# NeatoLDS_Breakout_Board_v0_1.net
KiCad netlist of a schematic drawn in EAGLE
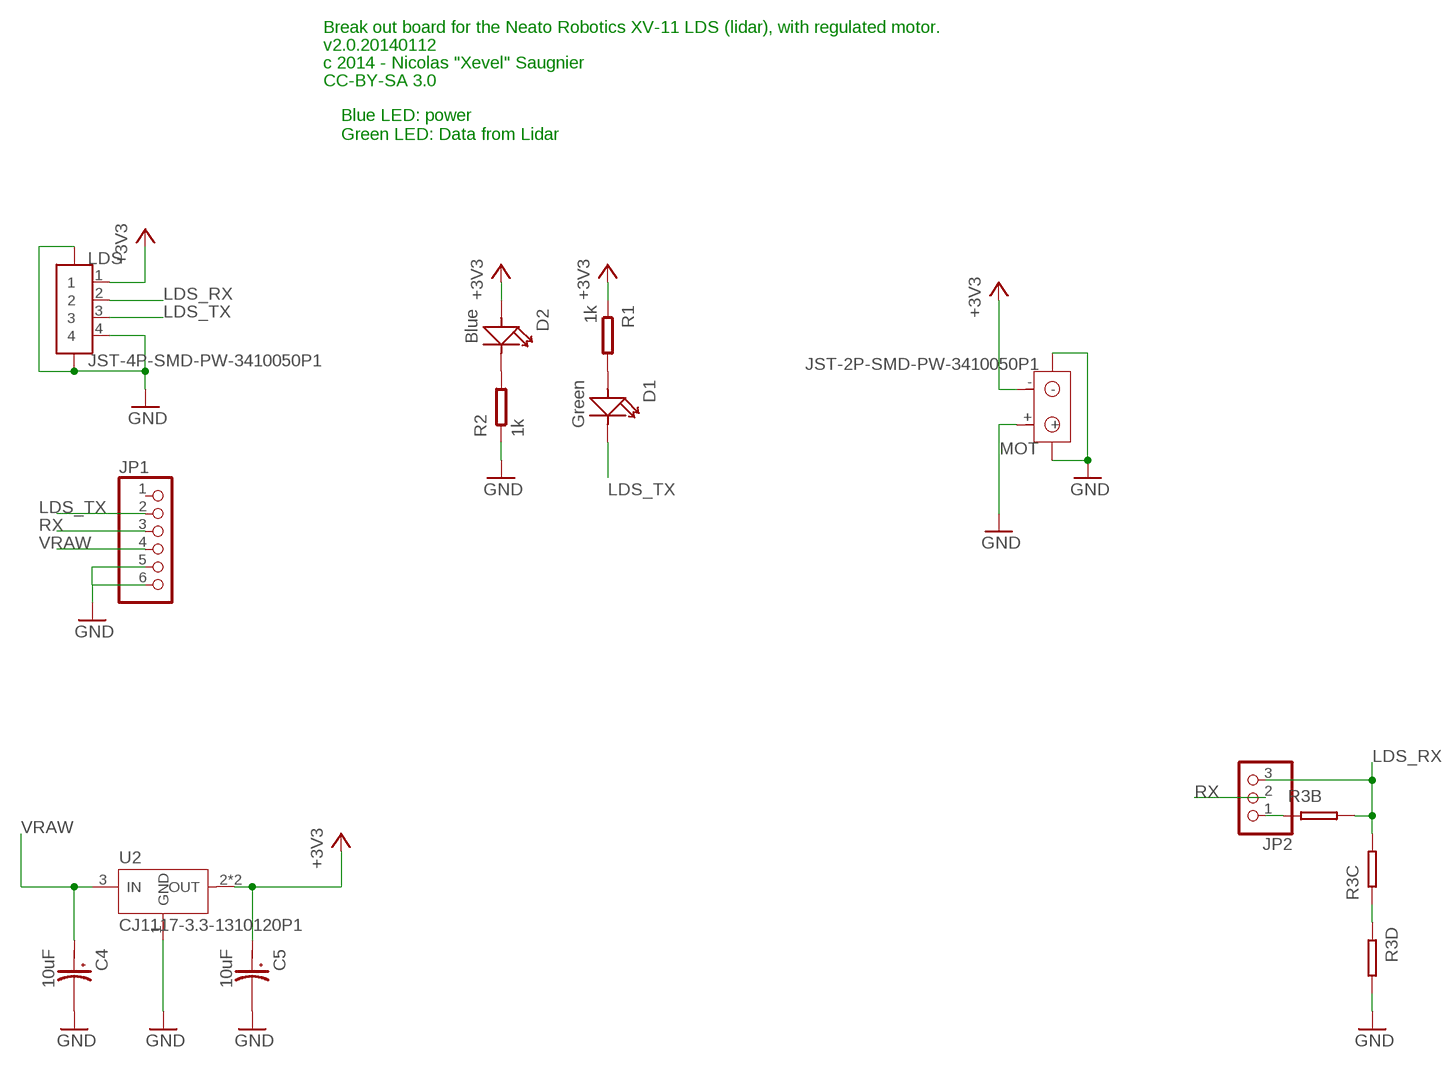
[diagram p0: schematic, sheet 1]

(export (version "E")
  (design (tool "Eeschema 10.0.6"))
  (components
    (comp (ref "C4")
      (value "10uF")
      (footprint "eagle-import:AVX-A")
      (libsource (lib "eagle-import") (part "C-POLAR-A"))
    )
    (comp (ref "C5")
      (value "10uF")
      (footprint "eagle-import:AVX-A")
      (libsource (lib "eagle-import") (part "C-POLAR-A"))
    )
    (comp (ref "D1")
      (value "Green")
      (footprint "eagle-import:LED0603")
      (libsource (lib "eagle-import") (part "LED"))
    )
    (comp (ref "D2")
      (value "Blue")
      (footprint "eagle-import:LED0603")
      (libsource (lib "eagle-import") (part "LED"))
    )
    (comp (ref "JP1")
      (value "PINHD-1X6")
      (footprint "eagle-import:1X06")
      (libsource (lib "eagle-import") (part "PINHD-1X6"))
    )
    (comp (ref "JP2")
      (value "PINHD-1X3")
      (footprint "eagle-import:1X03")
      (libsource (lib "eagle-import") (part "PINHD-1X3"))
    )
    (comp (ref "LDS")
      (value "JST-4P-SMD-PW-3410050P1")
      (footprint "eagle-import:CON-4P-SMD-2.0-90D")
      (libsource (lib "eagle-import") (part "JST-4P-SMD-PW-3410050P1"))
    )
    (comp (ref "MOT")
      (value "JST-2P-SMD-PW-3410050P1")
      (footprint "eagle-import:2P-SMD-2.0-90D")
      (libsource (lib "eagle-import") (part "JST-2P-SMD-PW-3410050P1"))
    )
    (comp (ref "R1")
      (value "1k")
      (footprint "eagle-import:R0603")
      (libsource (lib "eagle-import") (part "R-0603"))
    )
    (comp (ref "R2")
      (value "1k")
      (footprint "eagle-import:R0603")
      (libsource (lib "eagle-import") (part "R-0603"))
    )
    (comp (ref "R3")
      (value "R-4R")
      (footprint "eagle-import:R1206-8")
      (libsource (lib "eagle-import") (part "R-4R"))
    )
    (comp (ref "U2")
      (value "CJ1117-3.3-1310120P1")
      (footprint "eagle-import:SOT89")
      (libsource (lib "eagle-import") (part "CJ1117-3.3-1310120P1"))
    )
  )
  (nets
    (net (code "1") (name "+3V3") (class "Default")
      (node (ref "C5") (pin "+") (pinfunction "1_+") (pintype "bidirectional"))
      (node (ref "D2") (pin "+") (pinfunction "+_+") (pintype "passive"))
      (node (ref "LDS") (pin "1") (pinfunction "1_1") (pintype "bidirectional"))
      (node (ref "MOT") (pin "-") (pinfunction "-_-") (pintype "bidirectional"))
      (node (ref "R1") (pin "1") (pinfunction "1_1") (pintype "passive"))
      (node (ref "U2") (pin "2") (pinfunction "OUT_2") (pintype "bidirectional"))
      (node (ref "U2") (pin "4") (pinfunction "OUT_4") (pintype "bidirectional"))
    )
    (net (code "2") (name "/LDS_RX") (class "Default")
      (node (ref "JP2") (pin "3") (pinfunction "3_3") (pintype "passive"))
      (node (ref "LDS") (pin "2") (pinfunction "2_2") (pintype "bidirectional"))
      (node (ref "R3") (pin "6") (pinfunction "2_6") (pintype "passive"))
      (node (ref "R3") (pin "7") (pinfunction "2_7") (pintype "passive"))
    )
    (net (code "3") (name "/LDS_TX") (class "Default")
      (node (ref "D1") (pin "-") (pinfunction "-_-") (pintype "passive"))
      (node (ref "JP1") (pin "2") (pinfunction "2_2") (pintype "passive"))
      (node (ref "LDS") (pin "3") (pinfunction "3_3") (pintype "bidirectional"))
    )
    (net (code "4") (name "/RX") (class "Default")
      (node (ref "JP1") (pin "3") (pinfunction "3_3") (pintype "passive"))
      (node (ref "JP2") (pin "2") (pinfunction "2_2") (pintype "passive"))
    )
    (net (code "5") (name "/VRAW") (class "Default")
      (node (ref "C4") (pin "+") (pinfunction "1_+") (pintype "bidirectional"))
      (node (ref "JP1") (pin "4") (pinfunction "4_4") (pintype "passive"))
      (node (ref "U2") (pin "3") (pinfunction "IN_3") (pintype "bidirectional"))
    )
    (net (code "6") (name "GND") (class "Default")
      (node (ref "C4") (pin "-") (pinfunction "2_-") (pintype "bidirectional"))
      (node (ref "C5") (pin "-") (pinfunction "2_-") (pintype "bidirectional"))
      (node (ref "JP1") (pin "5") (pinfunction "5_5") (pintype "passive"))
      (node (ref "JP1") (pin "6") (pinfunction "6_6") (pintype "passive"))
      (node (ref "LDS") (pin "4") (pinfunction "4_4") (pintype "bidirectional"))
      (node (ref "LDS") (pin "5") (pinfunction "5_5") (pintype "bidirectional"))
      (node (ref "LDS") (pin "6") (pinfunction "6_6") (pintype "bidirectional"))
      (node (ref "MOT") (pin "+") (pinfunction "+_+") (pintype "bidirectional"))
      (node (ref "MOT") (pin "3") (pinfunction "3_3") (pintype "bidirectional"))
      (node (ref "MOT") (pin "4") (pinfunction "4_4") (pintype "bidirectional"))
      (node (ref "R2") (pin "1") (pinfunction "1_1") (pintype "passive"))
      (node (ref "R3") (pin "5") (pinfunction "2_5") (pintype "passive"))
      (node (ref "U2") (pin "1") (pinfunction "GND_1") (pintype "bidirectional"))
    )
    (net (code "7") (name "Net-(D1-Pad+)") (class "Default")
      (node (ref "D1") (pin "+") (pinfunction "+_+") (pintype "passive"))
      (node (ref "R1") (pin "2") (pinfunction "2_2") (pintype "passive"))
    )
    (net (code "8") (name "Net-(D2-Pad-)") (class "Default")
      (node (ref "D2") (pin "-") (pinfunction "-_-") (pintype "passive"))
      (node (ref "R2") (pin "2") (pinfunction "2_2") (pintype "passive"))
    )
    (net (code "9") (name "Net-(R3B-1)") (class "Default")
      (node (ref "JP2") (pin "1") (pinfunction "1_1") (pintype "passive"))
      (node (ref "R3") (pin "2") (pinfunction "1_2") (pintype "passive"))
    )
    (net (code "10") (name "Net-(R3C-1)") (class "Default")
      (node (ref "R3") (pin "3") (pinfunction "1_3") (pintype "passive"))
      (node (ref "R3") (pin "4") (pinfunction "1_4") (pintype "passive"))
    )
    (net (code "11") (name "unconnected-(JP1-Pad1)") (class "Default")
      (node (ref "JP1") (pin "1") (pinfunction "1_1") (pintype "passive"))
    )
  )
)
